# week7-small-noftdi.net
KiCad netlist of a schematic drawn in EAGLE
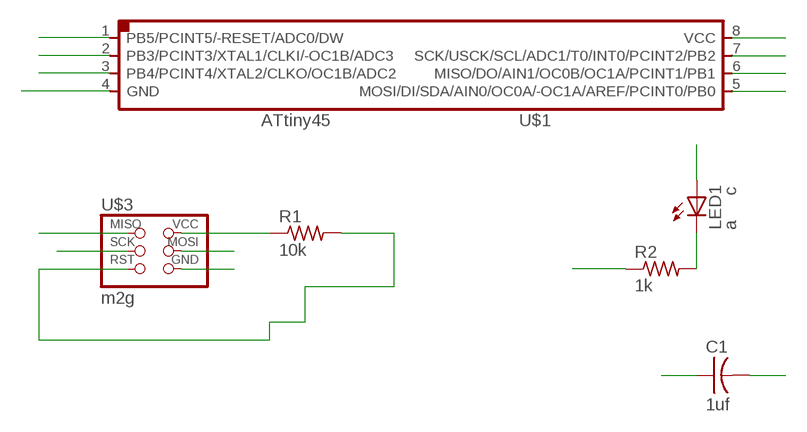
[diagram p0: schematic, sheet 1]

(export (version "E")
  (design (tool "Eeschema 10.0.6"))
  (components
    (comp (ref "C1")
      (value "1uf")
      (footprint "eagle-import:C1206FAB")
      (libsource (lib "eagle-import") (part "CAP-US1206FAB"))
    )
    (comp (ref "LED1")
      (value "a c")
      (footprint "eagle-import:LED1206FAB")
      (libsource (lib "eagle-import") (part "LEDFAB1206"))
    )
    (comp (ref "R1")
      (value "10k")
      (footprint "eagle-import:R1206FAB")
      (libsource (lib "eagle-import") (part "RES-US1206FAB"))
    )
    (comp (ref "R2")
      (value "1k")
      (footprint "eagle-import:R1206FAB")
      (libsource (lib "eagle-import") (part "RES-US1206FAB"))
    )
    (comp (ref "U$1")
      (value "tt45")
      (footprint "eagle-import:SOIC8")
      (libsource (lib "eagle-import") (part "ATTINY45SI"))
    )
    (comp (ref "U$3")
      (value "m2g")
      (footprint "eagle-import:2X03SMD")
      (libsource (lib "eagle-import") (part "AVRISPSMD"))
    )
  )
  (nets
    (net (code "1") (name "/GND") (class "Default")
      (node (ref "C1") (pin "2") (pinfunction "2_2") (pintype "passive"))
      (node (ref "R2") (pin "1") (pinfunction "1_1") (pintype "passive"))
      (node (ref "U$1") (pin "4") (pinfunction "GND_4") (pintype "bidirectional"))
      (node (ref "U$3") (pin "6") (pinfunction "GND_6") (pintype "passive"))
    )
    (net (code "2") (name "/MISO") (class "Default")
      (node (ref "U$1") (pin "6") (pinfunction "MISO/DO/AIN1/OC0B/OC1A/PCINT1/PB1_6") (pintype "bidirectional"))
      (node (ref "U$3") (pin "1") (pinfunction "MISO_1") (pintype "passive"))
    )
    (net (code "3") (name "/MOSI") (class "Default")
      (node (ref "U$1") (pin "5") (pinfunction "MOSI/DI/SDA/AIN0/OC0A/-OC1A/AREF/PCINT0/PB0_5") (pintype "bidirectional"))
      (node (ref "U$3") (pin "4") (pinfunction "MOSI_4") (pintype "passive"))
    )
    (net (code "4") (name "/RST") (class "Default")
      (node (ref "R1") (pin "2") (pinfunction "2_2") (pintype "passive"))
      (node (ref "U$1") (pin "1") (pinfunction "PB5/PCINT5/-RESET/ADC0/DW_1") (pintype "bidirectional"))
      (node (ref "U$3") (pin "5") (pinfunction "RST_5") (pintype "passive"))
    )
    (net (code "5") (name "/SCK") (class "Default")
      (node (ref "U$1") (pin "7") (pinfunction "SCK/USCK/SCL/ADC1/T0/INT0/PCINT2/PB2_7") (pintype "bidirectional"))
      (node (ref "U$3") (pin "3") (pinfunction "SCK_3") (pintype "passive"))
    )
    (net (code "6") (name "/VCC") (class "Default")
      (node (ref "C1") (pin "1") (pinfunction "1_1") (pintype "passive"))
      (node (ref "R1") (pin "1") (pinfunction "1_1") (pintype "passive"))
      (node (ref "U$1") (pin "8") (pinfunction "VCC_8") (pintype "bidirectional"))
      (node (ref "U$3") (pin "2") (pinfunction "VCC_2") (pintype "passive"))
    )
    (net (code "7") (name "/XTAL1") (class "Default")
      (node (ref "LED1") (pin "1") (pinfunction "A_1") (pintype "passive"))
      (node (ref "U$1") (pin "2") (pinfunction "PB3/PCINT3/XTAL1/CLKI/-OC1B/ADC3_2") (pintype "bidirectional"))
    )
    (net (code "8") (name "Net-(LED1-C)") (class "Default")
      (node (ref "LED1") (pin "2") (pinfunction "C_2") (pintype "passive"))
      (node (ref "R2") (pin "2") (pinfunction "2_2") (pintype "passive"))
    )
    (net (code "9") (name "unconnected-(U$1-PB4{slash}PCINT4{slash}XTAL2{slash}CLKO{slash}OC1B{slash}ADC2-Pad3)") (class "Default")
      (node (ref "U$1") (pin "3") (pinfunction "PB4/PCINT4/XTAL2/CLKO/OC1B/ADC2_3") (pintype "bidirectional"))
    )
  )
)
